# 05_ADC.net
KiCad netlist of a schematic drawn in Altium Designer
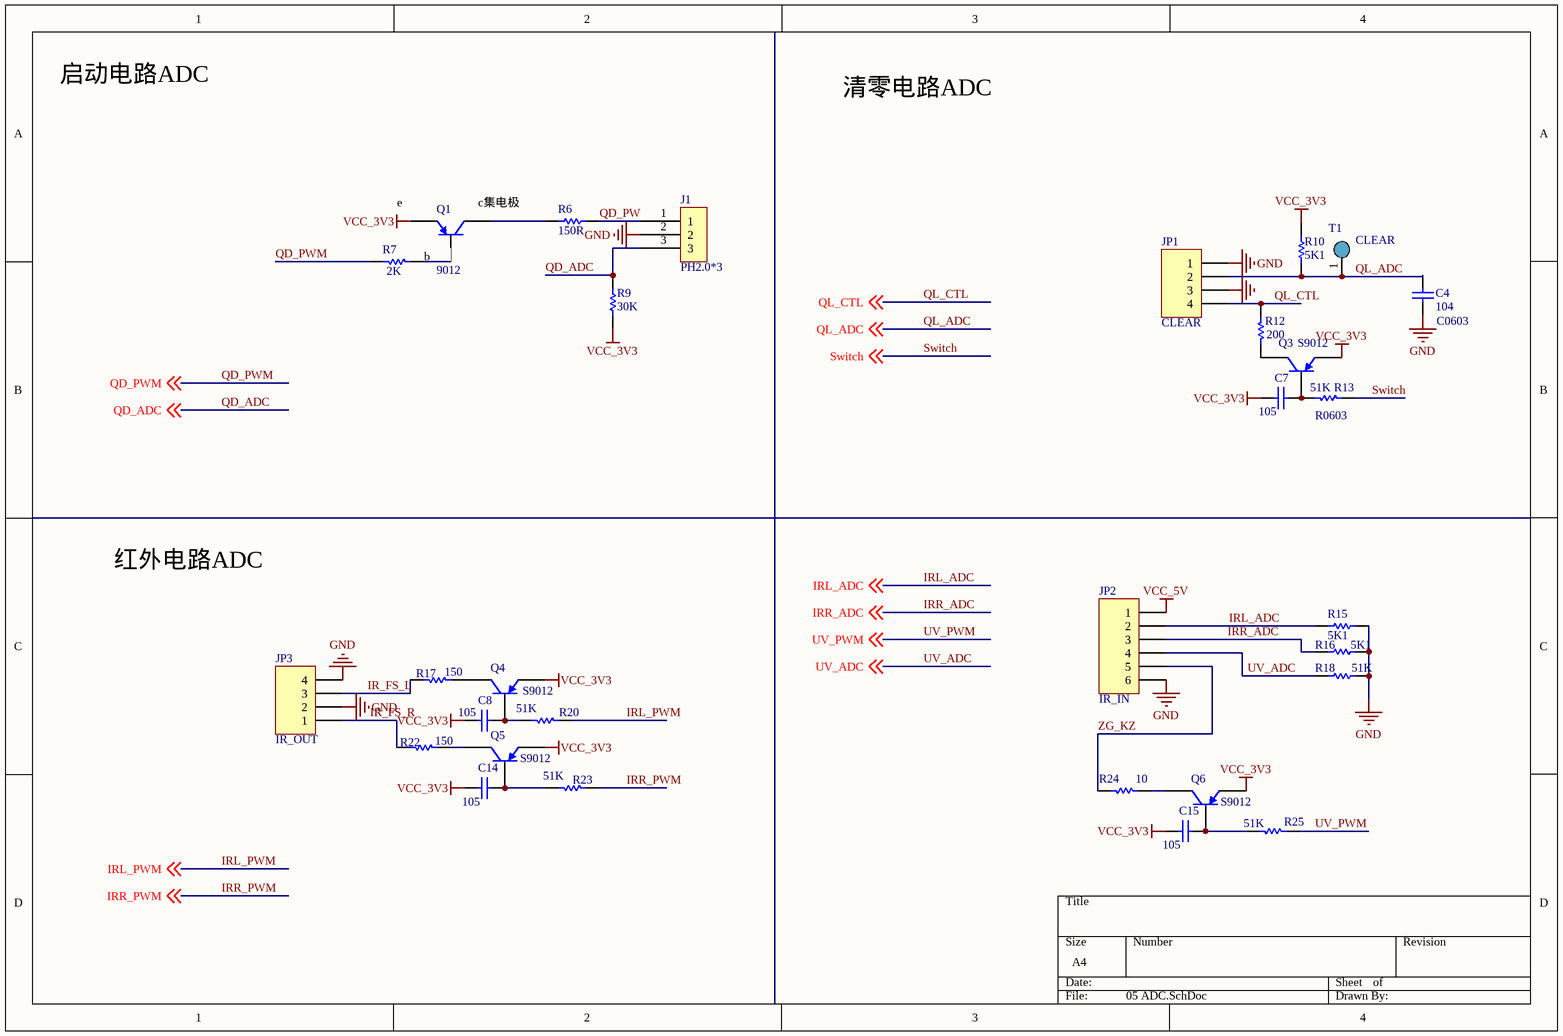
[diagram p0: 05 ADC.SchDoc]

(export (version "E")
  (design (tool "Eeschema 10.0.6"))
  (components
    (comp (ref "C4")
      (value "104")
      (footprint "C0603")
      (description "Capacitor")
      (fields
        (field (name "MANUFACTURER") "Generic Components")
        (field (name "PUBLISHER") "Altium Hobart Technology Centre")
      )
      (libsource (lib "") (part "Cap_1"))
    )
    (comp (ref "C7")
      (value "105")
      (footprint "C0603")
      (description "Capacitor")
      (fields
        (field (name "MANUFACTURER") "Generic Components")
        (field (name "PUBLISHER") "Altium Hobart Technology Centre")
      )
      (libsource (lib "Miscellaneous Devices") (part "Cap"))
    )
    (comp (ref "C8")
      (value "105")
      (footprint "C0603")
      (description "Capacitor")
      (fields
        (field (name "MANUFACTURER") "Generic Components")
        (field (name "PUBLISHER") "Altium Hobart Technology Centre")
      )
      (libsource (lib "") (part "Cap_2"))
    )
    (comp (ref "C14")
      (value "105")
      (footprint "C0603")
      (description "Capacitor")
      (fields
        (field (name "MANUFACTURER") "Generic Components")
        (field (name "PUBLISHER") "Altium Hobart Technology Centre")
      )
      (libsource (lib "Miscellaneous Devices") (part "Cap"))
    )
    (comp (ref "C15")
      (value "105")
      (footprint "C0603")
      (description "Capacitor")
      (fields
        (field (name "MANUFACTURER") "Generic Components")
        (field (name "PUBLISHER") "Altium Hobart Technology Centre")
      )
      (libsource (lib "Miscellaneous Devices") (part "Cap"))
    )
    (comp (ref "J1")
      (value "PH2.0*3")
      (footprint "PH2.0*3")
      (libsource (lib "Integrated_Library") (part "PH2.0*3"))
    )
    (comp (ref "JP1")
      (value "CLEAR")
      (footprint "PH2.0*4")
      (description "Header, 4-Pin")
      (fields (field (name "PUBLISHER") "Altium Limited"))
      (libsource (lib "Miscellaneous Connectors") (part "Header 4"))
    )
    (comp (ref "JP2")
      (value "IR_IN")
      (footprint "PH2.0*6")
      (description "Header, 6-Pin")
      (fields (field (name "PUBLISHER") "Altium Limited"))
      (libsource (lib "Miscellaneous Connectors") (part "Header 6"))
    )
    (comp (ref "JP3")
      (value "IR_OUT")
      (footprint "PH2.0*4")
      (description "Header, 4-Pin")
      (fields (field (name "MANUFACTURER") "Generic Components"))
      (libsource (lib "") (part "Header 4_1"))
    )
    (comp (ref "Q1")
      (value "9012")
      (footprint "PNP-SOT-23")
      (description "PNP General Purpose Amplifier")
      (fields (field (name "PUBLISHER") "Altium Limited"))
      (libsource (lib "Miscellaneous Devices") (part "2N3906"))
    )
    (comp (ref "Q3")
      (value "S9012")
      (footprint "PNP-SOT-23")
      (description "PNP General Purpose Amplifier")
      (fields (field (name "PUBLISHER") "Altium Limited"))
      (libsource (lib "Miscellaneous Devices") (part "2N3906"))
    )
    (comp (ref "Q4")
      (value "S9012")
      (footprint "PNP-SOT-23")
      (description "PNP General Purpose Amplifier")
      (fields (field (name "PUBLISHER") "Altium Limited"))
      (libsource (lib "Miscellaneous Devices") (part "2N3906"))
    )
    (comp (ref "Q5")
      (value "S9012")
      (footprint "PNP-SOT-23")
      (description "PNP General Purpose Amplifier")
      (fields (field (name "PUBLISHER") "Altium Limited"))
      (libsource (lib "Miscellaneous Devices") (part "2N3906"))
    )
    (comp (ref "Q6")
      (value "S9012")
      (footprint "PNP-SOT-23")
      (description "PNP General Purpose Amplifier")
      (fields (field (name "PUBLISHER") "Altium Limited"))
      (libsource (lib "Miscellaneous Devices") (part "2N3906"))
    )
    (comp (ref "R6")
      (value "150R")
      (footprint "R0603")
      (description "Resistor")
      (fields (field (name "PUBLISHER") "Altium Limited"))
      (libsource (lib "Miscellaneous Devices") (part "Res1"))
    )
    (comp (ref "R7")
      (value "2K")
      (footprint "R0603")
      (description "Resistor")
      (fields
        (field (name "MANUFACTURER") "Generic Components")
        (field (name "PUBLISHER") "Altium Hobart Technology Centre")
      )
      (libsource (lib "") (part "Res1_1"))
    )
    (comp (ref "R9")
      (value "30K")
      (footprint "R0603")
      (description "Resistor")
      (fields (field (name "PUBLISHER") "Altium Limited"))
      (libsource (lib "Miscellaneous Devices") (part "Res1"))
    )
    (comp (ref "R10")
      (value "5K1")
      (footprint "R0603")
      (description "Resistor")
      (fields
        (field (name "MANUFACTURER") "Generic Components")
        (field (name "PUBLISHER") "Altium Hobart Technology Centre")
      )
      (libsource (lib "Miscellaneous Devices") (part "Res1"))
    )
    (comp (ref "R12")
      (value "200")
      (footprint "R0603")
      (description "Resistor")
      (fields
        (field (name "MANUFACTURER") "Generic Components")
        (field (name "PUBLISHER") "Altium Hobart Technology Centre")
      )
      (libsource (lib "") (part "Res1_1"))
    )
    (comp (ref "R13")
      (value "51K")
      (footprint "R0603")
      (description "Resistor")
      (fields
        (field (name "MANUFACTURER") "Generic Components")
        (field (name "PUBLISHER") "Altium Hobart Technology Centre")
      )
      (libsource (lib "") (part "Res1_1"))
    )
    (comp (ref "R15")
      (value "5K1")
      (footprint "R0603")
      (description "Resistor")
      (fields
        (field (name "MANUFACTURER") "Generic Components")
        (field (name "PUBLISHER") "Altium Hobart Technology Centre")
      )
      (libsource (lib "Miscellaneous Devices") (part "Res1"))
    )
    (comp (ref "R16")
      (value "5K1")
      (footprint "R0603")
      (description "Resistor")
      (fields
        (field (name "MANUFACTURER") "Generic Components")
        (field (name "PUBLISHER") "Altium Hobart Technology Centre")
      )
      (libsource (lib "Miscellaneous Devices") (part "Res1"))
    )
    (comp (ref "R17")
      (value "150")
      (footprint "R0603")
      (description "Resistor")
      (fields
        (field (name "MANUFACTURER") "Generic Components")
        (field (name "PUBLISHER") "Altium Hobart Technology Centre")
      )
      (libsource (lib "") (part "Res1_1"))
    )
    (comp (ref "R18")
      (value "51K")
      (footprint "R0603")
      (description "Resistor")
      (fields
        (field (name "MANUFACTURER") "Generic Components")
        (field (name "PUBLISHER") "Altium Hobart Technology Centre")
      )
      (libsource (lib "Miscellaneous Devices") (part "Res1"))
    )
    (comp (ref "R20")
      (value "51K")
      (footprint "R0603")
      (description "Resistor")
      (fields
        (field (name "MANUFACTURER") "Generic Components")
        (field (name "PUBLISHER") "Altium Hobart Technology Centre")
      )
      (libsource (lib "") (part "Res1_1"))
    )
    (comp (ref "R22")
      (value "150")
      (footprint "R0603")
      (description "Resistor")
      (fields
        (field (name "MANUFACTURER") "Generic Components")
        (field (name "PUBLISHER") "Altium Hobart Technology Centre")
      )
      (libsource (lib "") (part "Res1_1"))
    )
    (comp (ref "R23")
      (value "51K")
      (footprint "R0603")
      (description "Resistor")
      (fields
        (field (name "MANUFACTURER") "Generic Components")
        (field (name "PUBLISHER") "Altium Hobart Technology Centre")
      )
      (libsource (lib "") (part "Res1_1"))
    )
    (comp (ref "R24")
      (value "10")
      (footprint "R0603")
      (description "Resistor")
      (fields
        (field (name "MANUFACTURER") "Generic Components")
        (field (name "PUBLISHER") "Altium Hobart Technology Centre")
      )
      (libsource (lib "") (part "Res1_1"))
    )
    (comp (ref "R25")
      (value "51K")
      (footprint "R0603")
      (description "Resistor")
      (fields
        (field (name "MANUFACTURER") "Generic Components")
        (field (name "PUBLISHER") "Altium Hobart Technology Centre")
      )
      (libsource (lib "") (part "Res1_1"))
    )
    (comp (ref "T1") (value "CLEAR") (footprint "测试点") (libsource (lib "CHQJ-SCH") (part "DIAN")))
  )
  (nets
    (net (code "1") (name "/IR_FS_L") (class "Default")
      (node (ref "JP3") (pin "3") (pinfunction "3_3") (pintype "passive"))
      (node (ref "R17") (pin "2") (pinfunction "2_2") (pintype "passive"))
    )
    (net (code "2") (name "/IR_FS_R") (class "Default")
      (node (ref "JP3") (pin "1") (pinfunction "1_1") (pintype "passive"))
      (node (ref "R22") (pin "2") (pinfunction "2_2") (pintype "passive"))
    )
    (net (code "3") (name "/QD_PW") (class "Default")
      (node (ref "J1") (pin "1") (pinfunction "1_1") (pintype "passive"))
      (node (ref "R6") (pin "2") (pinfunction "2_2") (pintype "passive"))
    )
    (net (code "4") (name "/ZG_KZ") (class "Default")
      (node (ref "JP2") (pin "5") (pinfunction "5_5") (pintype "passive"))
      (node (ref "R24") (pin "2") (pinfunction "2_2") (pintype "passive"))
    )
    (net (code "5") (name "GND") (class "Default")
      (node (ref "C4") (pin "2") (pinfunction "2_2") (pintype "passive"))
      (node (ref "J1") (pin "2") (pinfunction "2_2") (pintype "passive"))
      (node (ref "JP1") (pin "1") (pinfunction "1_1") (pintype "passive"))
      (node (ref "JP1") (pin "3") (pinfunction "3_3") (pintype "passive"))
      (node (ref "JP2") (pin "6") (pinfunction "6_6") (pintype "passive"))
      (node (ref "JP3") (pin "2") (pinfunction "2_2") (pintype "passive"))
      (node (ref "JP3") (pin "4") (pinfunction "4_4") (pintype "passive"))
      (node (ref "R15") (pin "2") (pinfunction "2_2") (pintype "passive"))
      (node (ref "R16") (pin "2") (pinfunction "2_2") (pintype "passive"))
      (node (ref "R18") (pin "2") (pinfunction "2_2") (pintype "passive"))
    )
    (net (code "6") (name "IRL_ADC") (class "Default")
      (node (ref "JP2") (pin "2") (pinfunction "2_2") (pintype "passive"))
      (node (ref "R15") (pin "1") (pinfunction "1_1") (pintype "passive"))
    )
    (net (code "7") (name "IRL_PWM") (class "Default")
      (node (ref "R20") (pin "1") (pinfunction "1_1") (pintype "passive"))
    )
    (net (code "8") (name "IRR_ADC") (class "Default")
      (node (ref "JP2") (pin "3") (pinfunction "3_3") (pintype "passive"))
      (node (ref "R16") (pin "1") (pinfunction "1_1") (pintype "passive"))
    )
    (net (code "9") (name "IRR_PWM") (class "Default")
      (node (ref "R23") (pin "1") (pinfunction "1_1") (pintype "passive"))
    )
    (net (code "10") (name "Net-(Q1-B)") (class "Default")
      (node (ref "Q1") (pin "2") (pinfunction "B_2") (pintype "passive"))
      (node (ref "R7") (pin "1") (pinfunction "1_1") (pintype "passive"))
    )
    (net (code "11") (name "Net-(Q1-C)") (class "Default")
      (node (ref "Q1") (pin "3") (pinfunction "C_3") (pintype "passive"))
      (node (ref "R6") (pin "1") (pinfunction "1_1") (pintype "passive"))
    )
    (net (code "12") (name "Net-(Q3-B)") (class "Default")
      (node (ref "C7") (pin "2") (pinfunction "2_2") (pintype "passive"))
      (node (ref "Q3") (pin "2") (pinfunction "B_2") (pintype "passive"))
      (node (ref "R13") (pin "2") (pinfunction "2_2") (pintype "passive"))
    )
    (net (code "13") (name "Net-(Q3-C)") (class "Default")
      (node (ref "Q3") (pin "3") (pinfunction "C_3") (pintype "passive"))
      (node (ref "R12") (pin "2") (pinfunction "2_2") (pintype "passive"))
    )
    (net (code "14") (name "Net-(Q4-B)") (class "Default")
      (node (ref "C8") (pin "1") (pinfunction "1_1") (pintype "passive"))
      (node (ref "Q4") (pin "2") (pinfunction "B_2") (pintype "passive"))
      (node (ref "R20") (pin "2") (pinfunction "2_2") (pintype "passive"))
    )
    (net (code "15") (name "Net-(Q4-C)") (class "Default")
      (node (ref "Q4") (pin "3") (pinfunction "C_3") (pintype "passive"))
      (node (ref "R17") (pin "1") (pinfunction "1_1") (pintype "passive"))
    )
    (net (code "16") (name "Net-(Q5-B)") (class "Default")
      (node (ref "C14") (pin "2") (pinfunction "2_2") (pintype "passive"))
      (node (ref "Q5") (pin "2") (pinfunction "B_2") (pintype "passive"))
      (node (ref "R23") (pin "2") (pinfunction "2_2") (pintype "passive"))
    )
    (net (code "17") (name "Net-(Q5-C)") (class "Default")
      (node (ref "Q5") (pin "3") (pinfunction "C_3") (pintype "passive"))
      (node (ref "R22") (pin "1") (pinfunction "1_1") (pintype "passive"))
    )
    (net (code "18") (name "Net-(Q6-B)") (class "Default")
      (node (ref "C15") (pin "2") (pinfunction "2_2") (pintype "passive"))
      (node (ref "Q6") (pin "2") (pinfunction "B_2") (pintype "passive"))
      (node (ref "R25") (pin "2") (pinfunction "2_2") (pintype "passive"))
    )
    (net (code "19") (name "Net-(Q6-C)") (class "Default")
      (node (ref "Q6") (pin "3") (pinfunction "C_3") (pintype "passive"))
      (node (ref "R24") (pin "1") (pinfunction "1_1") (pintype "passive"))
    )
    (net (code "20") (name "QD_ADC") (class "Default")
      (node (ref "J1") (pin "3") (pinfunction "3_3") (pintype "passive"))
      (node (ref "R9") (pin "1") (pinfunction "1_1") (pintype "passive"))
    )
    (net (code "21") (name "QD_PWM") (class "Default")
      (node (ref "R7") (pin "2") (pinfunction "2_2") (pintype "passive"))
    )
    (net (code "22") (name "QL_ADC") (class "Default")
      (node (ref "C4") (pin "1") (pinfunction "1_1") (pintype "passive"))
      (node (ref "JP1") (pin "2") (pinfunction "2_2") (pintype "passive"))
      (node (ref "R10") (pin "2") (pinfunction "2_2") (pintype "passive"))
      (node (ref "T1") (pin "1") (pintype "passive"))
    )
    (net (code "23") (name "QL_CTL") (class "Default")
      (node (ref "JP1") (pin "4") (pinfunction "4_4") (pintype "passive"))
      (node (ref "R12") (pin "1") (pinfunction "1_1") (pintype "passive"))
    )
    (net (code "24") (name "Switch") (class "Default")
      (node (ref "R13") (pin "1") (pinfunction "1_1") (pintype "passive"))
    )
    (net (code "25") (name "UV_ADC") (class "Default")
      (node (ref "JP2") (pin "4") (pinfunction "4_4") (pintype "passive"))
      (node (ref "R18") (pin "1") (pinfunction "1_1") (pintype "passive"))
    )
    (net (code "26") (name "UV_PWM") (class "Default")
      (node (ref "R25") (pin "1") (pinfunction "1_1") (pintype "passive"))
    )
    (net (code "27") (name "VCC_3V3") (class "Default")
      (node (ref "C14") (pin "1") (pinfunction "1_1") (pintype "passive"))
      (node (ref "C15") (pin "1") (pinfunction "1_1") (pintype "passive"))
      (node (ref "C7") (pin "1") (pinfunction "1_1") (pintype "passive"))
      (node (ref "C8") (pin "2") (pinfunction "2_2") (pintype "passive"))
      (node (ref "Q1") (pin "1") (pinfunction "E_1") (pintype "passive"))
      (node (ref "Q3") (pin "1") (pinfunction "E_1") (pintype "passive"))
      (node (ref "Q4") (pin "1") (pinfunction "E_1") (pintype "passive"))
      (node (ref "Q5") (pin "1") (pinfunction "E_1") (pintype "passive"))
      (node (ref "Q6") (pin "1") (pinfunction "E_1") (pintype "passive"))
      (node (ref "R10") (pin "1") (pinfunction "1_1") (pintype "passive"))
      (node (ref "R9") (pin "2") (pinfunction "2_2") (pintype "passive"))
    )
    (net (code "28") (name "VCC_5V") (class "Default")
      (node (ref "JP2") (pin "1") (pinfunction "1_1") (pintype "passive"))
    )
  )
)
